# Mini_sys.net
KiCad netlist of a schematic drawn in Altium Designer
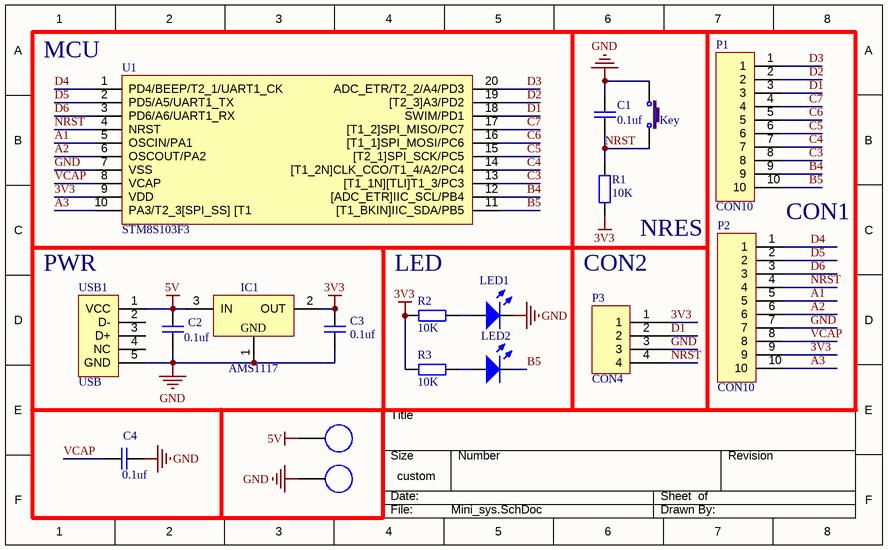
[diagram p0: Mini_sys.SchDoc]

(export (version "E")
  (design (tool "Eeschema 10.0.6"))
  (components
    (comp (ref "C1")
      (value "0.1uf")
      (footprint "C0603")
      (description "电容")
      (libsource (lib "Mini_sys_board") (part "Cap"))
    )
    (comp (ref "C2")
      (value "0.1uf")
      (footprint "C0603")
      (description "电容")
      (libsource (lib "Mini_sys_board") (part "Cap"))
    )
    (comp (ref "C3")
      (value "0.1uf")
      (footprint "C0603")
      (description "电容")
      (libsource (lib "Mini_sys_board") (part "Cap"))
    )
    (comp (ref "C4")
      (value "0.1uf")
      (footprint "C0603")
      (description "电容")
      (libsource (lib "Mini_sys_board") (part "Cap"))
    )
    (comp (ref "IC1")
      (value "AMS1117")
      (footprint "SOT223_N")
      (libsource (lib "Mini_sys_board") (part "AMS1117"))
    )
    (comp (ref "Key1")
      (value "Key")
      (footprint "TSW SMD-3*6*2.5")
      (description "按键")
      (libsource (lib "Mini_sys_board") (part "Key"))
    )
    (comp (ref "LED1") (value "LED") (footprint "LED 0805") (libsource (lib "Mini_sys_board") (part "LED")))
    (comp (ref "LED2") (value "LED") (footprint "LED 0805") (libsource (lib "Mini_sys_board") (part "LED")))
    (comp (ref "O1") (value "过孔") (footprint "过孔") (libsource (lib "Mini_sys_board") (part "过孔")))
    (comp (ref "O2") (value "过孔") (footprint "过孔") (libsource (lib "Mini_sys_board") (part "过孔")))
    (comp (ref "P1")
      (value "CON10")
      (footprint "HDR2.54-LI-10P")
      (description "插针")
      (libsource (lib "Mini_sys_board") (part "CON10"))
    )
    (comp (ref "P2")
      (value "CON10")
      (footprint "HDR2.54-LI-10P")
      (description "插针")
      (libsource (lib "Mini_sys_board") (part "CON10"))
    )
    (comp (ref "P3")
      (value "CON4")
      (footprint "HDR2.54-WI-4P")
      (libsource (lib "Mini_sys_board") (part "CON4"))
    )
    (comp (ref "R1")
      (value "10K")
      (footprint "R 0603")
      (description "电阻")
      (libsource (lib "Mini_sys_board") (part "Res"))
    )
    (comp (ref "R2")
      (value "10K")
      (footprint "0402r")
      (description "电阻")
      (libsource (lib "Mini_sys_board") (part "Res"))
    )
    (comp (ref "R3")
      (value "10K")
      (footprint "0402r")
      (description "电阻")
      (libsource (lib "Mini_sys_board") (part "Res"))
    )
    (comp (ref "U1")
      (value "STM8S103F3")
      (footprint "TSSOP20_L")
      (libsource (lib "Mini_sys_board") (part "STM8S103F3"))
    )
    (comp (ref "USB1")
      (value "USB")
      (footprint "USB-MICRO_E")
      (libsource (lib "Mini_sys_board") (part "USB"))
    )
  )
  (nets
    (net (code "1") (name "/A1") (class "Default")
      (node (ref "P2") (pin "5") (pinfunction "5_5") (pintype "passive"))
      (node (ref "U1") (pin "5") (pinfunction "OSCIN/PA1_5") (pintype "passive"))
    )
    (net (code "2") (name "/A2") (class "Default")
      (node (ref "P2") (pin "6") (pinfunction "6_6") (pintype "passive"))
      (node (ref "U1") (pin "6") (pinfunction "OSCOUT/PA2_6") (pintype "passive"))
    )
    (net (code "3") (name "/A3") (class "Default")
      (node (ref "P2") (pin "10") (pinfunction "10_10") (pintype "passive"))
      (node (ref "U1") (pin "10") (pinfunction "PA3/T2_3[SPI_SS]_[T1_10") (pintype "passive"))
    )
    (net (code "4") (name "/B4") (class "Default")
      (node (ref "P1") (pin "9") (pinfunction "9_9") (pintype "passive"))
      (node (ref "U1") (pin "12") (pinfunction "[ADC_ETR]IIC_SCL/PB4_12") (pintype "passive"))
    )
    (net (code "5") (name "/B5") (class "Default")
      (node (ref "LED2") (pin "2") (pinfunction "2_2") (pintype "passive"))
      (node (ref "P1") (pin "10") (pinfunction "10_10") (pintype "passive"))
      (node (ref "U1") (pin "11") (pinfunction "[T1_BKIN]IIC_SDA/PB5_11") (pintype "passive"))
    )
    (net (code "6") (name "/C3") (class "Default")
      (node (ref "P1") (pin "8") (pinfunction "8_8") (pintype "passive"))
      (node (ref "U1") (pin "13") (pinfunction "[T1_1N][TLI]T1_3/PC3_13") (pintype "passive"))
    )
    (net (code "7") (name "/C4") (class "Default")
      (node (ref "P1") (pin "7") (pinfunction "7_7") (pintype "passive"))
      (node (ref "U1") (pin "14") (pinfunction "[T1_2N]CLK_CCO/T1_4/A2/PC4_14") (pintype "passive"))
    )
    (net (code "8") (name "/C5") (class "Default")
      (node (ref "P1") (pin "6") (pinfunction "6_6") (pintype "passive"))
      (node (ref "U1") (pin "15") (pinfunction "[T2_1]SPI_SCK/PC5_15") (pintype "passive"))
    )
    (net (code "9") (name "/C6") (class "Default")
      (node (ref "P1") (pin "5") (pinfunction "5_5") (pintype "passive"))
      (node (ref "U1") (pin "16") (pinfunction "[T1_1]SPI_MOSI/PC6_16") (pintype "passive"))
    )
    (net (code "10") (name "/C7") (class "Default")
      (node (ref "P1") (pin "4") (pinfunction "4_4") (pintype "passive"))
      (node (ref "U1") (pin "17") (pinfunction "[T1_2]SPI_MISO/PC7_17") (pintype "passive"))
    )
    (net (code "11") (name "/D1") (class "Default")
      (node (ref "P1") (pin "3") (pinfunction "3_3") (pintype "passive"))
      (node (ref "P3") (pin "2") (pinfunction "2_2") (pintype "passive"))
      (node (ref "U1") (pin "18") (pinfunction "SWIM/PD1_18") (pintype "passive"))
    )
    (net (code "12") (name "/D2") (class "Default")
      (node (ref "P1") (pin "2") (pinfunction "2_2") (pintype "passive"))
      (node (ref "U1") (pin "19") (pinfunction "[T2_3]A3/PD2_19") (pintype "passive"))
    )
    (net (code "13") (name "/D3") (class "Default")
      (node (ref "P1") (pin "1") (pinfunction "1_1") (pintype "passive"))
      (node (ref "U1") (pin "20") (pinfunction "ADC_ETR/T2_2/A4/PD3_20") (pintype "passive"))
    )
    (net (code "14") (name "/D4") (class "Default")
      (node (ref "P2") (pin "1") (pinfunction "1_1") (pintype "passive"))
      (node (ref "U1") (pin "1") (pinfunction "PD4/BEEP/T2_1/UART1_CK_1") (pintype "passive"))
    )
    (net (code "15") (name "/D5") (class "Default")
      (node (ref "P2") (pin "2") (pinfunction "2_2") (pintype "passive"))
      (node (ref "U1") (pin "2") (pinfunction "PD5/A5/UART1_TX_2") (pintype "passive"))
    )
    (net (code "16") (name "/D6") (class "Default")
      (node (ref "P2") (pin "3") (pinfunction "3_3") (pintype "passive"))
      (node (ref "U1") (pin "3") (pinfunction "PD6/A6/UART1_RX_3") (pintype "passive"))
    )
    (net (code "17") (name "/NRST") (class "Default")
      (node (ref "C1") (pin "1") (pinfunction "1_1") (pintype "passive"))
      (node (ref "Key1") (pin "2") (pintype "passive"))
      (node (ref "P2") (pin "4") (pinfunction "4_4") (pintype "passive"))
      (node (ref "P3") (pin "4") (pinfunction "4_4") (pintype "passive"))
      (node (ref "R1") (pin "2") (pintype "passive"))
      (node (ref "U1") (pin "4") (pinfunction "NRST_4") (pintype "passive"))
    )
    (net (code "18") (name "/VCAP") (class "Default")
      (node (ref "C4") (pin "1") (pinfunction "1_1") (pintype "passive"))
      (node (ref "P2") (pin "8") (pinfunction "8_8") (pintype "passive"))
      (node (ref "U1") (pin "8") (pinfunction "VCAP_8") (pintype "passive"))
    )
    (net (code "19") (name "3V3") (class "Default")
      (node (ref "C3") (pin "1") (pinfunction "1_1") (pintype "passive"))
      (node (ref "IC1") (pin "2") (pinfunction "OUT_2") (pintype "passive"))
      (node (ref "P2") (pin "9") (pinfunction "9_9") (pintype "passive"))
      (node (ref "P3") (pin "1") (pinfunction "1_1") (pintype "passive"))
      (node (ref "R1") (pin "1") (pintype "passive"))
      (node (ref "R2") (pin "1") (pintype "passive"))
      (node (ref "R3") (pin "1") (pintype "passive"))
      (node (ref "U1") (pin "9") (pinfunction "VDD_9") (pintype "passive"))
    )
    (net (code "20") (name "5V") (class "Default")
      (node (ref "C2") (pin "1") (pinfunction "1_1") (pintype "passive"))
      (node (ref "IC1") (pin "3") (pinfunction "IN_3") (pintype "passive"))
      (node (ref "O1") (pin "0") (pinfunction "0_0") (pintype "passive"))
      (node (ref "USB1") (pin "1") (pinfunction "VCC_1") (pintype "passive"))
    )
    (net (code "21") (name "GND") (class "Default")
      (node (ref "C1") (pin "2") (pinfunction "2_2") (pintype "passive"))
      (node (ref "C2") (pin "2") (pinfunction "2_2") (pintype "passive"))
      (node (ref "C3") (pin "2") (pinfunction "2_2") (pintype "passive"))
      (node (ref "C4") (pin "2") (pinfunction "2_2") (pintype "passive"))
      (node (ref "IC1") (pin "1") (pinfunction "GND_1") (pintype "passive"))
      (node (ref "Key1") (pin "1") (pintype "passive"))
      (node (ref "LED1") (pin "2") (pinfunction "2_2") (pintype "passive"))
      (node (ref "O2") (pin "0") (pinfunction "0_0") (pintype "passive"))
      (node (ref "P2") (pin "7") (pinfunction "7_7") (pintype "passive"))
      (node (ref "P3") (pin "3") (pinfunction "3_3") (pintype "passive"))
      (node (ref "U1") (pin "7") (pinfunction "VSS_7") (pintype "passive"))
      (node (ref "USB1") (pin "5") (pinfunction "GND_5") (pintype "passive"))
    )
    (net (code "22") (name "Net-(LED1-3)") (class "Default")
      (node (ref "LED1") (pin "1") (pinfunction "3_1") (pintype "passive"))
      (node (ref "R2") (pin "2") (pintype "passive"))
    )
    (net (code "23") (name "Net-(LED2-3)") (class "Default")
      (node (ref "LED2") (pin "1") (pinfunction "3_1") (pintype "passive"))
      (node (ref "R3") (pin "2") (pintype "passive"))
    )
    (net (code "24") (name "unconnected-(USB1-D+-Pad3)") (class "Default")
      (node (ref "USB1") (pin "3") (pinfunction "D+_3") (pintype "passive"))
    )
    (net (code "25") (name "unconnected-(USB1-D--Pad2)") (class "Default")
      (node (ref "USB1") (pin "2") (pinfunction "D-_2") (pintype "passive"))
    )
    (net (code "26") (name "unconnected-(USB1-NC-Pad4)") (class "Default")
      (node (ref "USB1") (pin "4") (pinfunction "NC_4") (pintype "passive"))
    )
  )
)
